# 1-WireHumidityLight.net
KiCad netlist of a schematic drawn in EAGLE
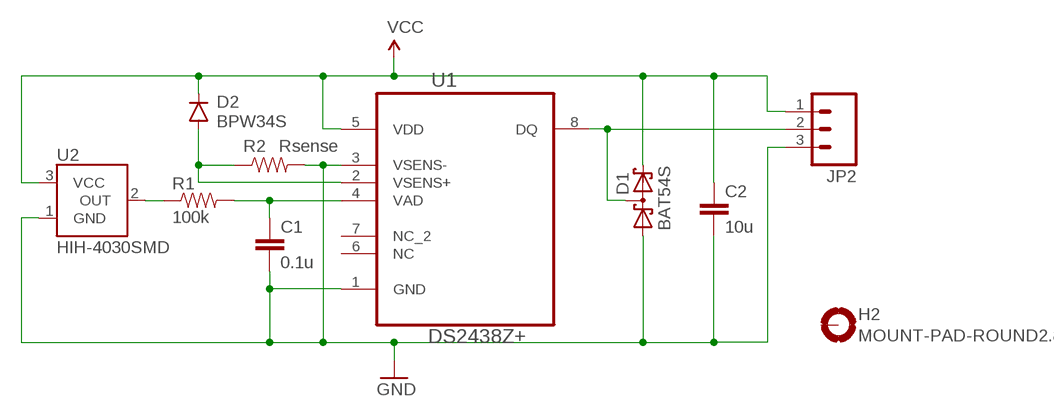
[diagram p0: schematic, sheet 1]

(export (version "E")
  (design (tool "Eeschema 10.0.6"))
  (components
    (comp (ref "C1")
      (value "0.1u")
      (footprint "eagle-import:0603-CAP")
      (libsource (lib "eagle-import") (part "CAP0603-CAP"))
    )
    (comp (ref "C2")
      (value "10u")
      (footprint "eagle-import:0603-CAP")
      (libsource (lib "eagle-import") (part "CAP0603-CAP"))
    )
    (comp (ref "D1")
      (value "BAT54S")
      (footprint "eagle-import:SOT23")
      (libsource (lib "eagle-import") (part "BAT54S"))
    )
    (comp (ref "D2")
      (value "BPW34S")
      (footprint "eagle-import:BPW34S")
      (libsource (lib "eagle-import") (part "BPW34SMD"))
    )
    (comp (ref "H2")
      (value "MOUNT-PAD-ROUND2.8")
      (footprint "eagle-import:2,8-PAD")
      (libsource (lib "eagle-import") (part "MOUNT-PAD-ROUND2.8"))
    )
    (comp (ref "JP2")
      (value "M03LONGPADS")
      (footprint "eagle-import:1X03_LONGPADS")
      (libsource (lib "eagle-import") (part "M03LONGPADS"))
    )
    (comp (ref "R1")
      (value "100k")
      (footprint "eagle-import:0603-RES")
      (libsource (lib "eagle-import") (part "RESISTOR0603-RES"))
    )
    (comp (ref "R2")
      (value "Rsense")
      (footprint "eagle-import:0603-RES")
      (libsource (lib "eagle-import") (part "RESISTOR0603-RES"))
    )
    (comp (ref "U1")
      (value "DS2438Z+")
      (footprint "eagle-import:SOIC127P600X175-8N")
      (libsource (lib "eagle-import") (part "DS2438Z+"))
    )
    (comp (ref "U2")
      (value "HIH-4030SMD")
      (footprint "eagle-import:HIH-4030")
      (libsource (lib "eagle-import") (part "HIH-4030SMD"))
    )
  )
  (nets
    (net (code "1") (name "GND") (class "Default")
      (node (ref "C1") (pin "2") (pinfunction "2_2") (pintype "passive"))
      (node (ref "C2") (pin "2") (pinfunction "2_2") (pintype "passive"))
      (node (ref "D1") (pin "1") (pinfunction "A1_1") (pintype "passive"))
      (node (ref "JP2") (pin "3") (pinfunction "3_3") (pintype "passive"))
      (node (ref "R2") (pin "2") (pinfunction "2_2") (pintype "passive"))
      (node (ref "U1") (pin "1") (pinfunction "GND_1") (pintype "passive"))
      (node (ref "U1") (pin "3") (pinfunction "VSENS-_3") (pintype "input"))
      (node (ref "U2") (pin "1") (pinfunction "GND_1") (pintype "bidirectional"))
    )
    (net (code "2") (name "Net-(D1-C1A2)") (class "Default")
      (node (ref "D1") (pin "3") (pinfunction "C1A2_3") (pintype "passive"))
      (node (ref "JP2") (pin "2") (pinfunction "2_2") (pintype "passive"))
      (node (ref "U1") (pin "8") (pinfunction "DQ_8") (pintype "bidirectional"))
    )
    (net (code "3") (name "Net-(D2-A)") (class "Default")
      (node (ref "D2") (pin "P$1") (pinfunction "A_P$1") (pintype "passive"))
      (node (ref "R2") (pin "1") (pinfunction "1_1") (pintype "passive"))
      (node (ref "U1") (pin "2") (pinfunction "VSENS+_2") (pintype "input"))
    )
    (net (code "4") (name "Net-(U1-VAD)") (class "Default")
      (node (ref "C1") (pin "1") (pinfunction "1_1") (pintype "passive"))
      (node (ref "R1") (pin "2") (pinfunction "2_2") (pintype "passive"))
      (node (ref "U1") (pin "4") (pinfunction "VAD_4") (pintype "input"))
    )
    (net (code "5") (name "Net-(U2-OUT)") (class "Default")
      (node (ref "R1") (pin "1") (pinfunction "1_1") (pintype "passive"))
      (node (ref "U2") (pin "2") (pinfunction "OUT_2") (pintype "bidirectional"))
    )
    (net (code "6") (name "VCC") (class "Default")
      (node (ref "C2") (pin "1") (pinfunction "1_1") (pintype "passive"))
      (node (ref "D1") (pin "2") (pinfunction "C2_2") (pintype "passive"))
      (node (ref "D2") (pin "P$2") (pinfunction "C_P$2") (pintype "passive"))
      (node (ref "JP2") (pin "1") (pinfunction "1_1") (pintype "passive"))
      (node (ref "U1") (pin "5") (pinfunction "VDD_5") (pintype "power_in"))
      (node (ref "U2") (pin "3") (pinfunction "VCC_3") (pintype "bidirectional"))
    )
    (net (code "7") (name "unconnected-(H2-MOUNT-PadB2,8)") (class "Default")
      (node (ref "H2") (pin "B2,8") (pinfunction "MOUNT_B2,8") (pintype "passive"))
    )
    (net (code "8") (name "unconnected-(U1-NC-Pad6)") (class "Default")
      (node (ref "U1") (pin "6") (pinfunction "NC_6") (pintype "no_connect"))
    )
    (net (code "9") (name "unconnected-(U1-NC_2-Pad7)") (class "Default")
      (node (ref "U1") (pin "7") (pinfunction "NC_2_7") (pintype "no_connect"))
    )
  )
)
